# DRV8301.net
KiCad netlist of a schematic drawn in Altium Designer
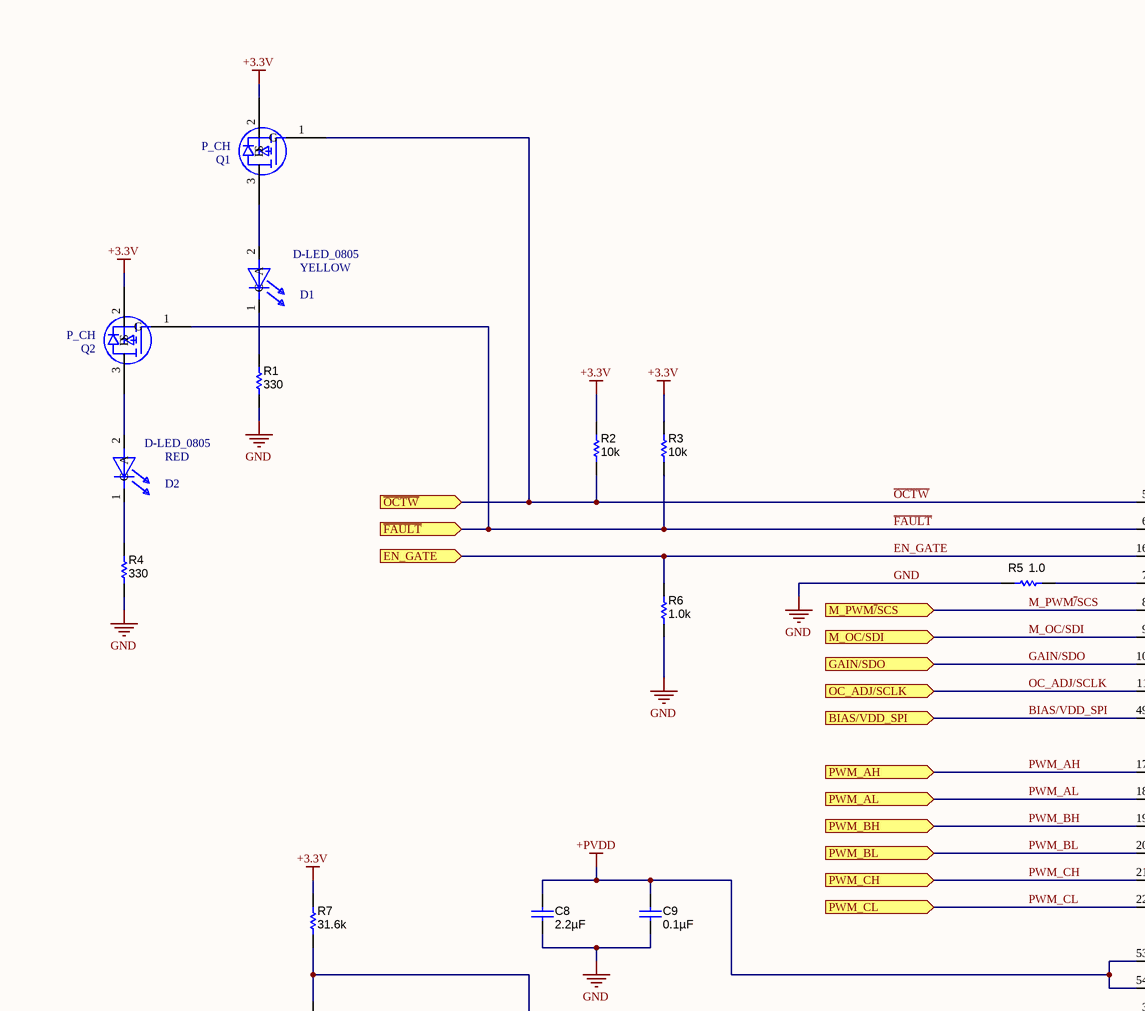
[diagram p0: DRV8301.SchDoc, top left]
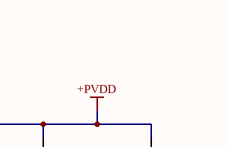
[diagram p1: DRV8301.SchDoc, top right]
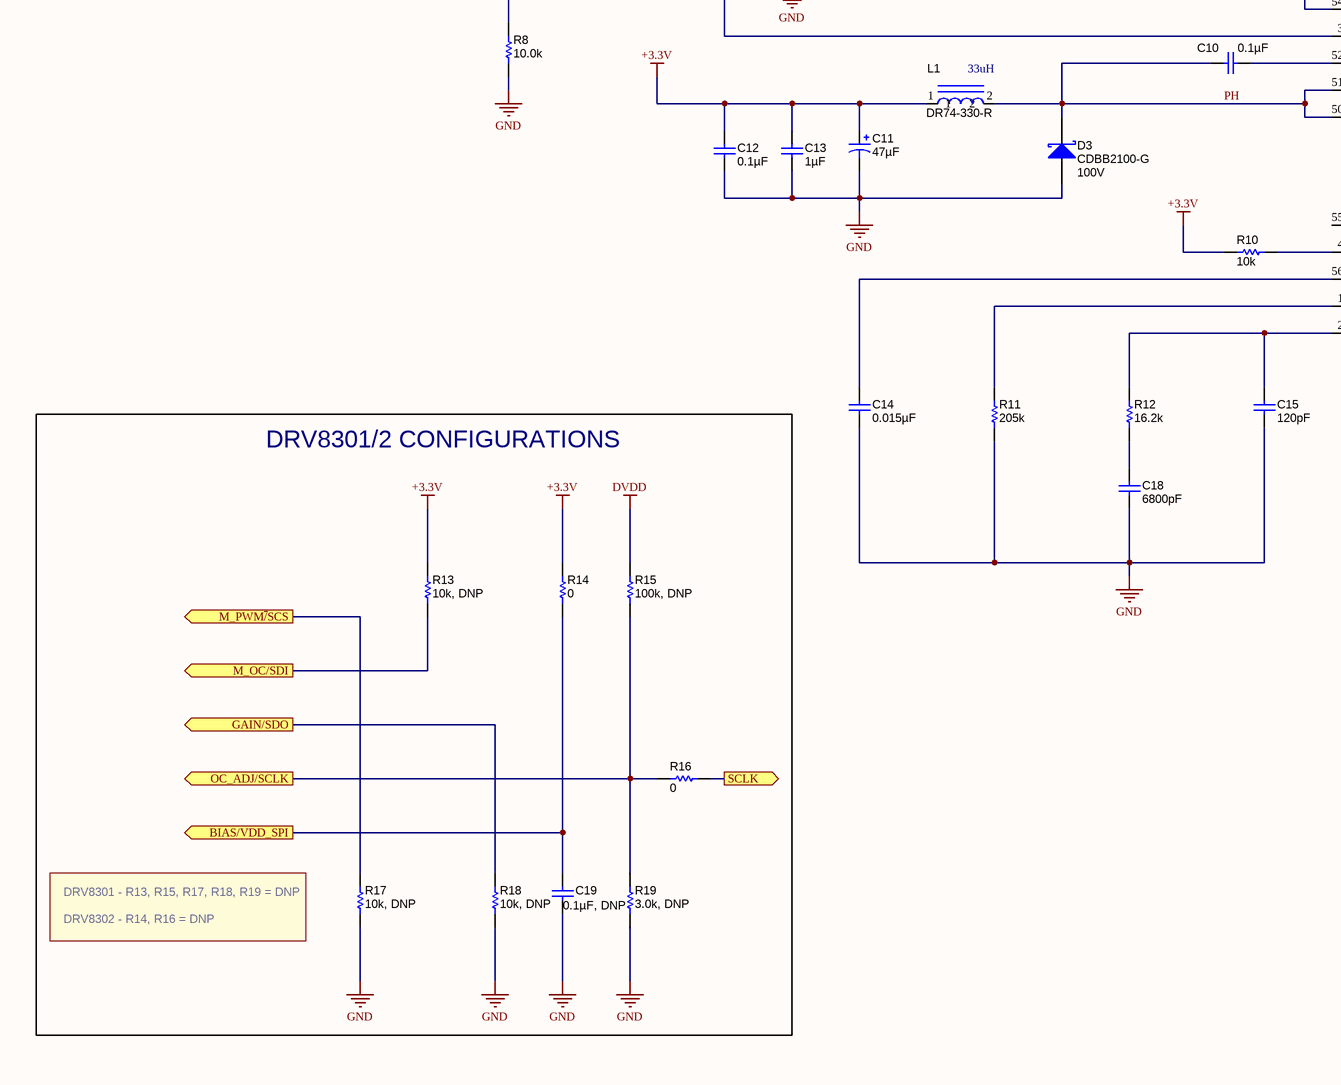
[diagram p2: DRV8301.SchDoc, bottom left]
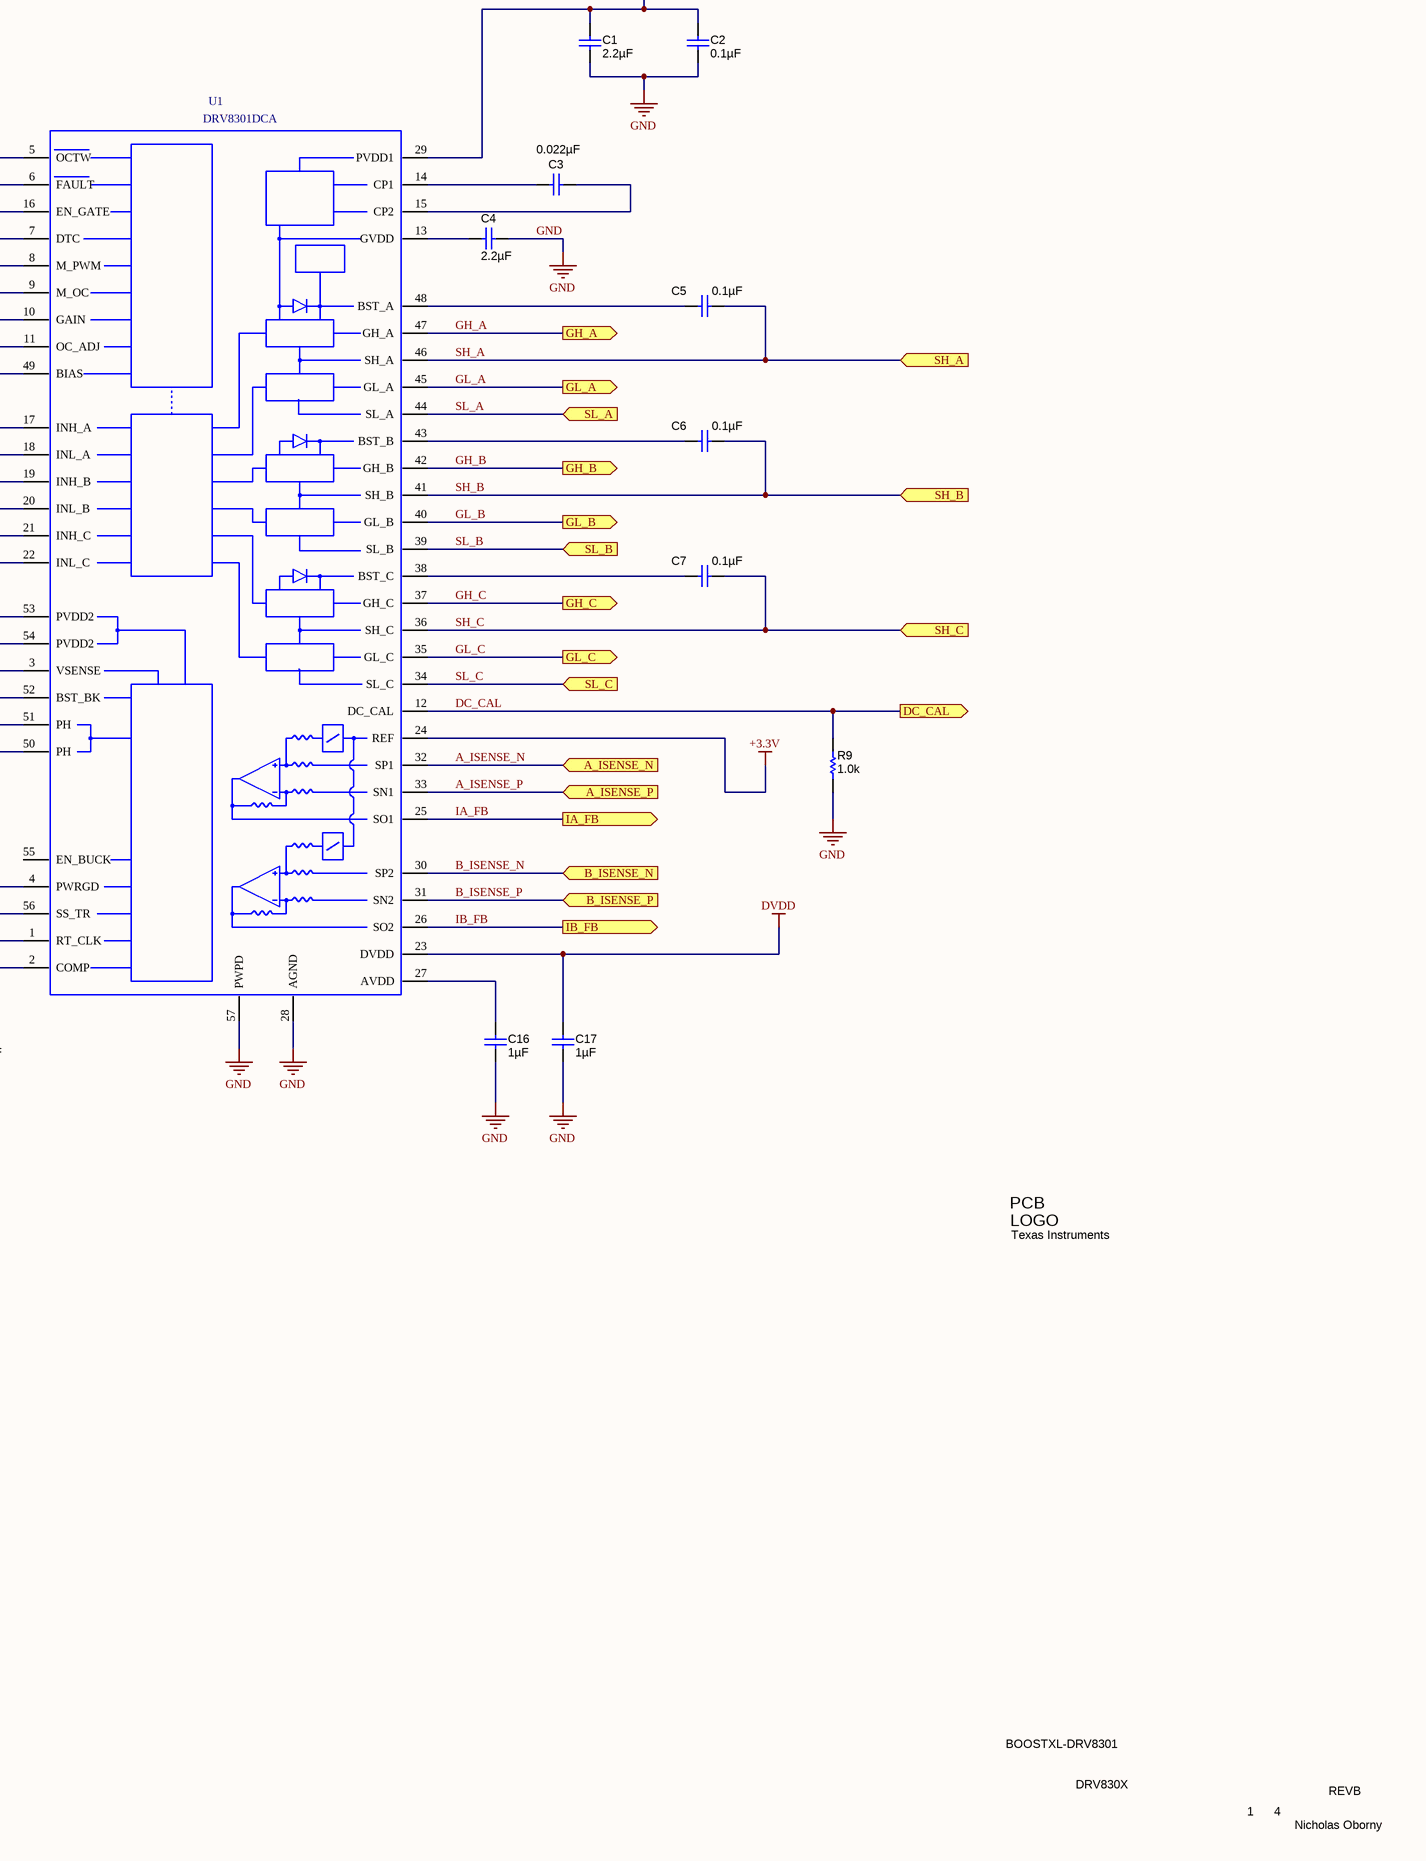
[diagram p3: DRV8301.SchDoc, bottom right]

(export (version "E")
  (design (tool "Eeschema 10.0.6"))
  (components
    (comp (ref "C1")
      (value "GRM32ER72A225KA35L")
      (footprint "1210L")
      (description "CAP, CERM, 2.2uF, 100V, +/-10%, X7R, 1210")
      (fields
        (field (name "VALUEDISPLAYED") "2.2µF")
        (field (name "MANUFACTURER") "MuRata")
        (field (name "PUBLISHER") "Texas Instruments")
      )
      (libsource (lib "Capacitor_Ceramic") (part "GRM32ER72A225KA35L"))
    )
    (comp (ref "C2")
      (value "GRM188R72A104KA35D")
      (footprint "0603L")
      (description "CAP, CERM, 0.1uF, 100V, +/-10%, X7R, 0603")
      (fields
        (field (name "VALUEDISPLAYED") "0.1µF")
        (field (name "MANUFACTURER") "MuRata")
        (field (name "PUBLISHER") "Texas Instruments")
      )
      (libsource (lib "Capacitor_Ceramic") (part "GRM188R72A104KA35D"))
    )
    (comp (ref "C3")
      (value "C1608X7R1H223K")
      (footprint "0603L")
      (description "CAP, CERM, 0.022uF, 50V, +/-10%, X7R, 0603")
      (fields
        (field (name "VALUEDISPLAYED") "0.022µF")
        (field (name "MANUFACTURER") "TDK")
        (field (name "PUBLISHER") "Texas Instruments")
      )
      (libsource (lib "Capacitor_Ceramic") (part "C1608X7R1H223K"))
    )
    (comp (ref "C4")
      (value "GRM219R61E225KA12D")
      (footprint "0805L")
      (description "CAP, CERM, 2.2uF, 25V, +/-10%, X5R, 0805")
      (fields
        (field (name "VALUEDISPLAYED") "2.2µF")
        (field (name "MANUFACTURER") "MuRata")
        (field (name "PUBLISHER") "Texas Instruments")
      )
      (libsource (lib "Capacitor_Ceramic") (part "GRM219R61E225KA12D"))
    )
    (comp (ref "C5")
      (value "C1608X7R1H104K")
      (footprint "0603L")
      (description "CAP, CERM, 0.1uF, 50V, +/-10%, X7R, 0603")
      (fields
        (field (name "VALUEDISPLAYED") "0.1µF")
        (field (name "MANUFACTURER") "TDK")
        (field (name "PUBLISHER") "Texas Instruments")
      )
      (libsource (lib "Capacitor_Ceramic") (part "C1608X7R1H104K"))
    )
    (comp (ref "C6")
      (value "C1608X7R1H104K")
      (footprint "0603L")
      (description "CAP, CERM, 0.1uF, 50V, +/-10%, X7R, 0603")
      (fields
        (field (name "VALUEDISPLAYED") "0.1µF")
        (field (name "MANUFACTURER") "TDK")
        (field (name "PUBLISHER") "Texas Instruments")
      )
      (libsource (lib "Capacitor_Ceramic") (part "C1608X7R1H104K"))
    )
    (comp (ref "C7")
      (value "C1608X7R1H104K")
      (footprint "0603L")
      (description "CAP, CERM, 0.1uF, 50V, +/-10%, X7R, 0603")
      (fields
        (field (name "VALUEDISPLAYED") "0.1µF")
        (field (name "MANUFACTURER") "TDK")
        (field (name "PUBLISHER") "Texas Instruments")
      )
      (libsource (lib "Capacitor_Ceramic") (part "C1608X7R1H104K"))
    )
    (comp (ref "C8")
      (value "GRM32ER72A225KA35L")
      (footprint "1210L")
      (description "CAP, CERM, 2.2uF, 100V, +/-10%, X7R, 1210")
      (fields
        (field (name "VALUEDISPLAYED") "2.2µF")
        (field (name "MANUFACTURER") "MuRata")
        (field (name "PUBLISHER") "Texas Instruments")
      )
      (libsource (lib "Capacitor_Ceramic") (part "GRM32ER72A225KA35L"))
    )
    (comp (ref "C9")
      (value "GRM188R72A104KA35D")
      (footprint "0603L")
      (description "CAP, CERM, 0.1uF, 100V, +/-10%, X7R, 0603")
      (fields
        (field (name "VALUEDISPLAYED") "0.1µF")
        (field (name "MANUFACTURER") "MuRata")
        (field (name "PUBLISHER") "Texas Instruments")
      )
      (libsource (lib "Capacitor_Ceramic") (part "GRM188R72A104KA35D"))
    )
    (comp (ref "C10")
      (value "C1608X7R1H104K")
      (footprint "0603L")
      (description "CAP, CERM, 0.1uF, 50V, +/-10%, X7R, 0603")
      (fields
        (field (name "VALUEDISPLAYED") "0.1µF")
        (field (name "MANUFACTURER") "TDK")
        (field (name "PUBLISHER") "Texas Instruments")
      )
      (libsource (lib "Capacitor_Ceramic") (part "C1608X7R1H104K"))
    )
    (comp (ref "C11")
      (value "EEE-FK1E470P")
      (footprint "SM_RADIAL_D")
      (description "CAP, AL, 47uF, 25V, +/-20%, 0.36 ohm, SMD")
      (fields
        (field (name "VALUEDISPLAYED") "47µF")
        (field (name "MANUFACTURER") "Panasonic")
        (field (name "PUBLISHER") "Texas Instruments")
      )
      (libsource (lib "Capacitor_Aluminum") (part "EEE-FK1E470P"))
    )
    (comp (ref "C12")
      (value "C1608X7R1E104K")
      (footprint "0603L")
      (description "CAP, CERM, 0.1uF, 25V, +/-10%, X7R, 0603")
      (fields
        (field (name "VALUEDISPLAYED") "0.1µF")
        (field (name "MANUFACTURER") "TDK")
        (field (name "PUBLISHER") "Texas Instruments")
      )
      (libsource (lib "Capacitor_Ceramic") (part "C1608X7R1E104K"))
    )
    (comp (ref "C13")
      (value "C1608X5R1E105K080AC")
      (footprint "0603L")
      (description "CAP, CERM, 1uF, 25V, +/-10%, X5R, 0603")
      (fields
        (field (name "VALUEDISPLAYED") "1µF")
        (field (name "MANUFACTURER") "TDK")
        (field (name "PUBLISHER") "Texas Instruments")
      )
      (libsource (lib "Capacitor_Ceramic") (part "C1608X5R1E105K080AC"))
    )
    (comp (ref "C14")
      (value "GRM188R71H153KA01D")
      (footprint "0603L")
      (description "CAP, CERM, 0.015uF, 50V, +/-10%, X7R, 0603")
      (fields
        (field (name "VALUEDISPLAYED") "0.015µF")
        (field (name "MANUFACTURER") "MuRata")
        (field (name "PUBLISHER") "Texas Instruments")
      )
      (libsource (lib "Capacitor_Ceramic") (part "GRM188R71H153KA01D"))
    )
    (comp (ref "C15")
      (value "GRM1885C1H121JA01D")
      (footprint "0603L")
      (description "CAP, CERM, 120pF, 50V, +/-5%, C0G/NP0, 0603")
      (fields
        (field (name "VALUEDISPLAYED") "120pF")
        (field (name "MANUFACTURER") "MuRata")
        (field (name "PUBLISHER") "Texas Instruments")
      )
      (libsource (lib "Capacitor_Ceramic") (part "GRM1885C1H121JA01D"))
    )
    (comp (ref "C16")
      (value "GRM188R61E105KA12D")
      (footprint "0603L")
      (description "CAP, CERM, 1uF, 25V, +/-10%, X5R, 0603")
      (fields
        (field (name "VALUEDISPLAYED") "1µF")
        (field (name "MANUFACTURER") "MuRata")
        (field (name "PUBLISHER") "Texas Instruments")
      )
      (libsource (lib "Capacitor_Ceramic") (part "GRM188R61E105KA12D"))
    )
    (comp (ref "C17")
      (value "GRM188R61E105KA12D")
      (footprint "0603L")
      (description "CAP, CERM, 1uF, 25V, +/-10%, X5R, 0603")
      (fields
        (field (name "VALUEDISPLAYED") "1µF")
        (field (name "MANUFACTURER") "MuRata")
        (field (name "PUBLISHER") "Texas Instruments")
      )
      (libsource (lib "Capacitor_Ceramic") (part "GRM188R61E105KA12D"))
    )
    (comp (ref "C18")
      (value "GRM188R71H682KA01D")
      (footprint "0603L")
      (description "CAP, CERM, 6800pF, 50V, +/-10%, X7R, 0603")
      (fields
        (field (name "VALUEDISPLAYED") "6800pF")
        (field (name "MANUFACTURER") "MuRata")
        (field (name "PUBLISHER") "Texas Instruments")
      )
      (libsource (lib "Capacitor_Ceramic") (part "GRM188R71H682KA01D"))
    )
    (comp (ref "C19")
      (value "C1608X7R1E104K")
      (footprint "0603L")
      (description "CAP, CERM, 0.1uF, 25V, +/-10%, X7R, 0603")
      (fields
        (field (name "VALUEDISPLAYED") "0.1µF, DNP")
        (field (name "MANUFACTURER") "TDK")
        (field (name "PUBLISHER") "Texas Instruments")
      )
      (libsource (lib "Capacitor_Ceramic") (part "C1608X7R1E104K"))
    )
    (comp (ref "D1")
      (value "D-LED_0805")
      (footprint "LED_0805")
      (description "LED THIN 585NM YEL DIFF 0805 SMD")
      (fields
        (field (name "PARTNUMBER") "SML-LXT0805YW-TR")
        (field (name "ALTIUM_VALUE") "YELLOW")
        (field (name "MANUFACTURER") "Lumex Opto/Components Inc")
      )
      (libsource (lib "*") (part "D-LED_0805"))
    )
    (comp (ref "D2")
      (value "D-LED_0805")
      (footprint "LED_0805")
      (description "LED THIN660NM SUPRED DIFF0805SMD")
      (fields
        (field (name "PARTNUMBER") "SML-LXT0805SRW-TR")
        (field (name "ALTIUM_VALUE") "RED")
        (field (name "MANUFACTURER") "Lumex Opto/Components Inc")
      )
      (libsource (lib "*") (part "D-LED_0805"))
    )
    (comp (ref "D3")
      (value "CDBB2100-G")
      (footprint "SMB")
      (description "Diode, Schottky, 100V, 2A, SMB")
      (fields
        (field (name "ALTIUM_VALUE") "100V")
        (field (name "MANUFACTURER") "Comchip Technology")
        (field (name "PUBLISHER") "Texas Instruments")
      )
      (libsource (lib "Diode") (part "CDBC5100-G"))
    )
    (comp (ref "L1")
      (value "DR74-330-R")
      (footprint "IND_DR74")
      (description "INDUCTOR SHIELD PWR 33UH SMD")
      (fields (field (name "MANUFACTURER") "Cooper Bussmann") (field (name "ALTIUM_VALUE") "33uH"))
      (libsource (lib "PADSlegacy_Passive") (part "IND_DR74-XXX"))
    )
    (comp (ref "Logo1")
      (value "Texas Instruments")
      (footprint "TI_Symbol_Overlay_Small")
      (description "Texas Instrument Corporate Signature")
      (fields (field (name "SYMBOLCREATOR") "codlsc") (field (name "PUBLISHER") "Texas Instruments"))
      (libsource (lib "Logos") (part "TI_Logo"))
    )
    (comp (ref "Q1")
      (value "P_CH")
      (footprint "SOT-23")
      (description "MOSFET P-CH 8V 5.4A SOT23-3")
      (fields (field (name "PARTNUMBER") "SI2325DS-T1-E3") (field (name "MANUFACTURER") "Vishey Siliconix"))
      (libsource (lib "*") (part "TR_PFET_SOT23"))
    )
    (comp (ref "Q2")
      (value "P_CH")
      (footprint "SOT-23")
      (description "MOSFET P-CH 8V 5.4A SOT23-3")
      (fields (field (name "PARTNUMBER") "SI2325DS-T1-E3") (field (name "MANUFACTURER") "Vishey Siliconix"))
      (libsource (lib "*") (part "TR_PFET_SOT23"))
    )
    (comp (ref "R1")
      (value "330")
      (footprint "0603L")
      (description "RES, 330 ohm, 5%, 0.1W, 0603")
      (fields
        (field (name "PARTNUMBER") "CRCW0603330RJNEA")
        (field (name "MANUFACTURER") "Vishay-Dale")
        (field (name "PUBLISHER") "Texas Instruments")
      )
      (libsource (lib "Resistor_0603") (part "CRCW0603330RJNEA"))
    )
    (comp (ref "R2")
      (value "10k")
      (footprint "0603L")
      (description "RES, 10k ohm, 5%, 0.1W, 0603")
      (fields
        (field (name "PARTNUMBER") "CRCW060310K0JNEA")
        (field (name "MANUFACTURER") "Vishay-Dale")
        (field (name "PUBLISHER") "Texas Instruments")
      )
      (libsource (lib "Resistor_0603") (part "CRCW060310K0JNEA"))
    )
    (comp (ref "R3")
      (value "10k")
      (footprint "0603L")
      (description "RES, 10k ohm, 5%, 0.1W, 0603")
      (fields
        (field (name "PARTNUMBER") "CRCW060310K0JNEA")
        (field (name "MANUFACTURER") "Vishay-Dale")
        (field (name "PUBLISHER") "Texas Instruments")
      )
      (libsource (lib "Resistor_0603") (part "CRCW060310K0JNEA"))
    )
    (comp (ref "R4")
      (value "330")
      (footprint "0603L")
      (description "RES, 330 ohm, 5%, 0.1W, 0603")
      (fields
        (field (name "PARTNUMBER") "CRCW0603330RJNEA")
        (field (name "MANUFACTURER") "Vishay-Dale")
        (field (name "PUBLISHER") "Texas Instruments")
      )
      (libsource (lib "Resistor_0603") (part "CRCW0603330RJNEA"))
    )
    (comp (ref "R5")
      (value "1.0")
      (footprint "0603L")
      (description "RES, 1.0 ohm, 5%, 0.1W, 0603")
      (fields
        (field (name "PARTNUMBER") "CRCW06031R00JNEA")
        (field (name "MANUFACTURER") "Vishay-Dale")
        (field (name "PUBLISHER") "Texas Instruments")
      )
      (libsource (lib "Resistor_0603") (part "CRCW06031R00JNEA"))
    )
    (comp (ref "R6")
      (value "1.0k")
      (footprint "0603L")
      (description "RES, 1.0k ohm, 5%, 0.1W, 0603")
      (fields
        (field (name "PARTNUMBER") "CRCW06031K00JNEA")
        (field (name "MANUFACTURER") "Vishay-Dale")
        (field (name "PUBLISHER") "Texas Instruments")
      )
      (libsource (lib "Resistor_0603") (part "CRCW06031K00JNEA"))
    )
    (comp (ref "R7")
      (value "31.6k")
      (footprint "0603L")
      (description "RES, 31.6k ohm, 1%, 0.1W, 0603")
      (fields
        (field (name "PARTNUMBER") "CRCW060331K6FKEA")
        (field (name "MANUFACTURER") "Vishay-Dale")
        (field (name "PUBLISHER") "Texas Instruments")
      )
      (libsource (lib "Resistor_0603") (part "CRCW060331K6FKEA"))
    )
    (comp (ref "R8")
      (value "10.0k")
      (footprint "0603L")
      (description "RES, 10.0k ohm, 0.1%, 0.1W, 0603")
      (fields
        (field (name "PARTNUMBER") "RG1608P-103-B-T5")
        (field (name "MANUFACTURER") "Susumu Co Ltd")
        (field (name "PUBLISHER") "Texas Instruments")
      )
      (libsource (lib "Resistor_0603") (part "RG1608P-103-B-T5"))
    )
    (comp (ref "R9")
      (value "1.0k")
      (footprint "0603L")
      (description "RES, 1.0k ohm, 5%, 0.1W, 0603")
      (fields
        (field (name "PARTNUMBER") "CRCW06031K00JNEA")
        (field (name "MANUFACTURER") "Vishay-Dale")
        (field (name "PUBLISHER") "Texas Instruments")
      )
      (libsource (lib "Resistor_0603") (part "CRCW06031K00JNEA"))
    )
    (comp (ref "R10")
      (value "10k")
      (footprint "0603L")
      (description "RES, 10k ohm, 5%, 0.1W, 0603")
      (fields
        (field (name "PARTNUMBER") "CRCW060310K0JNEA")
        (field (name "MANUFACTURER") "Vishay-Dale")
        (field (name "PUBLISHER") "Texas Instruments")
      )
      (libsource (lib "Resistor_0603") (part "CRCW060310K0JNEA"))
    )
    (comp (ref "R11")
      (value "205k")
      (footprint "0603L")
      (description "RES, 205k ohm, 1%, 0.1W, 0603")
      (fields
        (field (name "PARTNUMBER") "CRCW0603205KFKEA")
        (field (name "MANUFACTURER") "Vishay-Dale")
        (field (name "PUBLISHER") "Texas Instruments")
      )
      (libsource (lib "Resistor_0603") (part "CRCW0603205KFKEA"))
    )
    (comp (ref "R12")
      (value "16.2k")
      (footprint "0603L")
      (description "RES, 16.2k ohm, 1%, 0.1W, 0603")
      (fields
        (field (name "PARTNUMBER") "CRCW060316K2FKEA")
        (field (name "MANUFACTURER") "Vishay-Dale")
        (field (name "PUBLISHER") "Texas Instruments")
      )
      (libsource (lib "Resistor_0603") (part "CRCW060316K2FKEA"))
    )
    (comp (ref "R13")
      (value "10k, DNP")
      (footprint "0603L")
      (description "RES, 10k ohm, 5%, 0.1W, 0603")
      (fields
        (field (name "PARTNUMBER") "CRCW060310K0JNEA")
        (field (name "MANUFACTURER") "Vishay-Dale")
        (field (name "PUBLISHER") "Texas Instruments")
      )
      (libsource (lib "Resistor_0603") (part "CRCW060310K0JNEA"))
    )
    (comp (ref "R14")
      (value "0")
      (footprint "0603L")
      (description "RES, 0 ohm, 5%, 0.1W, 0603")
      (fields
        (field (name "PARTNUMBER") "CRCW06030000Z0EA")
        (field (name "MANUFACTURER") "Vishay-Dale")
        (field (name "PUBLISHER") "Texas Instruments")
      )
      (libsource (lib "Resistor_0603") (part "CRCW06030000Z0EA"))
    )
    (comp (ref "R15")
      (value "100k, DNP")
      (footprint "0603L")
      (description "RES, 100k ohm, 5%, 0.1W, 0603")
      (fields
        (field (name "PARTNUMBER") "CRCW0603100KJNEA")
        (field (name "MANUFACTURER") "Vishay-Dale")
        (field (name "PUBLISHER") "Texas Instruments")
      )
      (libsource (lib "Resistor_0603") (part "CRCW0603100KJNEA"))
    )
    (comp (ref "R16")
      (value "0")
      (footprint "0603L")
      (description "RES, 0 ohm, 5%, 0.1W, 0603")
      (fields
        (field (name "PARTNUMBER") "CRCW06030000Z0EA")
        (field (name "MANUFACTURER") "Vishay-Dale")
        (field (name "PUBLISHER") "Texas Instruments")
      )
      (libsource (lib "Resistor_0603") (part "CRCW06030000Z0EA"))
    )
    (comp (ref "R17")
      (value "10k, DNP")
      (footprint "0603L")
      (description "RES, 10k ohm, 5%, 0.1W, 0603")
      (fields
        (field (name "PARTNUMBER") "CRCW060310K0JNEA")
        (field (name "MANUFACTURER") "Vishay-Dale")
        (field (name "PUBLISHER") "Texas Instruments")
      )
      (libsource (lib "Resistor_0603") (part "CRCW060310K0JNEA"))
    )
    (comp (ref "R18")
      (value "10k, DNP")
      (footprint "0603L")
      (description "RES, 10k ohm, 5%, 0.1W, 0603")
      (fields
        (field (name "PARTNUMBER") "CRCW060310K0JNEA")
        (field (name "MANUFACTURER") "Vishay-Dale")
        (field (name "PUBLISHER") "Texas Instruments")
      )
      (libsource (lib "Resistor_0603") (part "CRCW060310K0JNEA"))
    )
    (comp (ref "R19")
      (value "3.0k, DNP")
      (footprint "0603L")
      (description "RES, 3.0k ohm, 5%, 0.1W, 0603")
      (fields
        (field (name "PARTNUMBER") "CRCW06033K00JNEA")
        (field (name "MANUFACTURER") "Vishay-Dale")
        (field (name "PUBLISHER") "Texas Instruments")
      )
      (libsource (lib "Resistor_0603") (part "CRCW06033K00JNEA"))
    )
    (comp (ref "U1")
      (value "DRV8301DCA")
      (footprint "DCA_56P")
      (description "IC, 3 Phase Pre-Driver with Dual Current Shunt Amplifiers and Buck Regulator-Hardware Controlled")
      (fields (field (name "MANUFACTURER") "Texas Instruments") (field (name "VENDOR PART #") "Supplied"))
      (libsource (lib "*") (part "DRV8302DCA_ERIC"))
    )
  )
  (nets
    (net (code "1") (name "+3.3V") (class "Default")
      (node (ref "C11") (pin "1") (pinfunction "+_1") (pintype "passive"))
      (node (ref "C12") (pin "1") (pinfunction "1_1") (pintype "passive"))
      (node (ref "C13") (pin "1") (pinfunction "1_1") (pintype "passive"))
      (node (ref "L1") (pin "1") (pinfunction "1_1") (pintype "passive"))
      (node (ref "Q1") (pin "2") (pinfunction "S_2") (pintype "passive"))
      (node (ref "Q2") (pin "2") (pinfunction "S_2") (pintype "passive"))
      (node (ref "R10") (pin "2") (pinfunction "2_2") (pintype "passive"))
      (node (ref "R13") (pin "2") (pinfunction "2_2") (pintype "passive"))
      (node (ref "R14") (pin "2") (pinfunction "2_2") (pintype "passive"))
      (node (ref "R2") (pin "2") (pinfunction "2_2") (pintype "passive"))
      (node (ref "R3") (pin "2") (pinfunction "2_2") (pintype "passive"))
      (node (ref "R7") (pin "2") (pinfunction "2_2") (pintype "passive"))
      (node (ref "U1") (pin "24") (pinfunction "REF_24") (pintype "passive"))
    )
    (net (code "2") (name "+PVDD") (class "Default")
      (node (ref "C1") (pin "1") (pinfunction "1_1") (pintype "passive"))
      (node (ref "C2") (pin "1") (pinfunction "1_1") (pintype "passive"))
      (node (ref "C8") (pin "1") (pinfunction "1_1") (pintype "passive"))
      (node (ref "C9") (pin "1") (pinfunction "1_1") (pintype "passive"))
      (node (ref "U1") (pin "29") (pinfunction "PVDD1_29") (pintype "passive"))
      (node (ref "U1") (pin "53") (pinfunction "PVDD2_53") (pintype "passive"))
      (node (ref "U1") (pin "54") (pinfunction "PVDD2_54") (pintype "passive"))
    )
    (net (code "3") (name "/A_ISENSE_N") (class "Default")
      (node (ref "U1") (pin "32") (pinfunction "SP1_32") (pintype "passive"))
    )
    (net (code "4") (name "/A_ISENSE_P") (class "Default")
      (node (ref "U1") (pin "33") (pinfunction "SN1_33") (pintype "passive"))
    )
    (net (code "5") (name "/BIAS{slash}VDD_SPI") (class "Default")
      (node (ref "C19") (pin "1") (pinfunction "1_1") (pintype "passive"))
      (node (ref "R14") (pin "1") (pinfunction "1_1") (pintype "passive"))
      (node (ref "U1") (pin "49") (pinfunction "BIAS_49") (pintype "passive"))
    )
    (net (code "6") (name "/B_ISENSE_N") (class "Default")
      (node (ref "U1") (pin "30") (pinfunction "SP2_30") (pintype "passive"))
    )
    (net (code "7") (name "/B_ISENSE_P") (class "Default")
      (node (ref "U1") (pin "31") (pinfunction "SN2_31") (pintype "passive"))
    )
    (net (code "8") (name "/DC_CAL") (class "Default")
      (node (ref "R9") (pin "2") (pinfunction "2_2") (pintype "passive"))
      (node (ref "U1") (pin "12") (pinfunction "DC_CAL_12") (pintype "passive"))
    )
    (net (code "9") (name "/EN_GATE") (class "Default")
      (node (ref "R6") (pin "2") (pinfunction "2_2") (pintype "passive"))
      (node (ref "U1") (pin "16") (pinfunction "EN_GATE_16") (pintype "passive"))
    )
    (net (code "10") (name "/FAULT") (class "Default")
      (node (ref "Q2") (pin "1") (pinfunction "G_1") (pintype "passive"))
      (node (ref "R3") (pin "1") (pinfunction "1_1") (pintype "passive"))
      (node (ref "U1") (pin "6") (pinfunction "FAULT_6") (pintype "passive"))
    )
    (net (code "11") (name "/GAIN{slash}SDO") (class "Default")
      (node (ref "R18") (pin "2") (pinfunction "2_2") (pintype "passive"))
      (node (ref "U1") (pin "10") (pinfunction "GAIN_10") (pintype "passive"))
    )
    (net (code "12") (name "/GH_A") (class "Default")
      (node (ref "U1") (pin "47") (pinfunction "GH_A_47") (pintype "passive"))
    )
    (net (code "13") (name "/GH_B") (class "Default")
      (node (ref "U1") (pin "42") (pinfunction "GH_B_42") (pintype "passive"))
    )
    (net (code "14") (name "/GH_C") (class "Default")
      (node (ref "U1") (pin "37") (pinfunction "GH_C_37") (pintype "passive"))
    )
    (net (code "15") (name "/GL_A") (class "Default")
      (node (ref "U1") (pin "45") (pinfunction "GL_A_45") (pintype "passive"))
    )
    (net (code "16") (name "/GL_B") (class "Default")
      (node (ref "U1") (pin "40") (pinfunction "GL_B_40") (pintype "passive"))
    )
    (net (code "17") (name "/GL_C") (class "Default")
      (node (ref "U1") (pin "35") (pinfunction "GL_C_35") (pintype "passive"))
    )
    (net (code "18") (name "/IA_FB") (class "Default")
      (node (ref "U1") (pin "25") (pinfunction "SO1_25") (pintype "passive"))
    )
    (net (code "19") (name "/IB_FB") (class "Default")
      (node (ref "U1") (pin "26") (pinfunction "SO2_26") (pintype "passive"))
    )
    (net (code "20") (name "/M_OC{slash}SDI") (class "Default")
      (node (ref "R13") (pin "1") (pinfunction "1_1") (pintype "passive"))
      (node (ref "U1") (pin "9") (pinfunction "M_OC_9") (pintype "passive"))
    )
    (net (code "21") (name "/M_PWM~{{slash}}SCS") (class "Default")
      (node (ref "R17") (pin "2") (pinfunction "2_2") (pintype "passive"))
      (node (ref "U1") (pin "8") (pinfunction "M_PWM_8") (pintype "passive"))
    )
    (net (code "22") (name "/OCTW") (class "Default")
      (node (ref "Q1") (pin "1") (pinfunction "G_1") (pintype "passive"))
      (node (ref "R2") (pin "1") (pinfunction "1_1") (pintype "passive"))
      (node (ref "U1") (pin "5") (pinfunction "OCTW_5") (pintype "passive"))
    )
    (net (code "23") (name "/OC_ADJ{slash}SCLK") (class "Default")
      (node (ref "R15") (pin "2") (pinfunction "2_2") (pintype "passive"))
      (node (ref "R16") (pin "2") (pinfunction "2_2") (pintype "passive"))
      (node (ref "R19") (pin "2") (pinfunction "2_2") (pintype "passive"))
      (node (ref "U1") (pin "11") (pinfunction "OC_ADJ_11") (pintype "passive"))
    )
    (net (code "24") (name "/PH") (class "Default")
      (node (ref "C10") (pin "1") (pinfunction "1_1") (pintype "passive"))
      (node (ref "D3") (pin "1") (pinfunction "K_1") (pintype "passive"))
      (node (ref "L1") (pin "2") (pinfunction "2_2") (pintype "passive"))
      (node (ref "U1") (pin "50") (pinfunction "PH_50") (pintype "passive"))
      (node (ref "U1") (pin "51") (pinfunction "PH_51") (pintype "passive"))
    )
    (net (code "25") (name "/PWM_AH") (class "Default")
      (node (ref "U1") (pin "17") (pinfunction "INH_A_17") (pintype "passive"))
    )
    (net (code "26") (name "/PWM_AL") (class "Default")
      (node (ref "U1") (pin "18") (pinfunction "INL_A_18") (pintype "passive"))
    )
    (net (code "27") (name "/PWM_BH") (class "Default")
      (node (ref "U1") (pin "19") (pinfunction "INH_B_19") (pintype "passive"))
    )
    (net (code "28") (name "/PWM_BL") (class "Default")
      (node (ref "U1") (pin "20") (pinfunction "INL_B_20") (pintype "passive"))
    )
    (net (code "29") (name "/PWM_CH") (class "Default")
      (node (ref "U1") (pin "21") (pinfunction "INH_C_21") (pintype "passive"))
    )
    (net (code "30") (name "/PWM_CL") (class "Default")
      (node (ref "U1") (pin "22") (pinfunction "INL_C_22") (pintype "passive"))
    )
    (net (code "31") (name "/SCLK") (class "Default")
      (node (ref "R16") (pin "1") (pinfunction "1_1") (pintype "passive"))
    )
    (net (code "32") (name "/SH_A") (class "Default")
      (node (ref "C5") (pin "2") (pinfunction "2_2") (pintype "passive"))
      (node (ref "U1") (pin "46") (pinfunction "SH_A_46") (pintype "passive"))
    )
    (net (code "33") (name "/SH_B") (class "Default")
      (node (ref "C6") (pin "2") (pinfunction "2_2") (pintype "passive"))
      (node (ref "U1") (pin "41") (pinfunction "SH_B_41") (pintype "passive"))
    )
    (net (code "34") (name "/SH_C") (class "Default")
      (node (ref "C7") (pin "2") (pinfunction "2_2") (pintype "passive"))
      (node (ref "U1") (pin "36") (pinfunction "SH_C_36") (pintype "passive"))
    )
    (net (code "35") (name "/SL_A") (class "Default")
      (node (ref "U1") (pin "44") (pinfunction "SL_A_44") (pintype "passive"))
    )
    (net (code "36") (name "/SL_B") (class "Default")
      (node (ref "U1") (pin "39") (pinfunction "SL_B_39") (pintype "passive"))
    )
    (net (code "37") (name "/SL_C") (class "Default")
      (node (ref "U1") (pin "34") (pinfunction "SL_C_34") (pintype "passive"))
    )
    (net (code "38") (name "DVDD") (class "Default")
      (node (ref "C17") (pin "1") (pinfunction "1_1") (pintype "passive"))
      (node (ref "R15") (pin "1") (pinfunction "1_1") (pintype "passive"))
      (node (ref "U1") (pin "23") (pinfunction "DVDD_23") (pintype "passive"))
    )
    (net (code "39") (name "GND") (class "Default")
      (node (ref "C1") (pin "2") (pinfunction "2_2") (pintype "passive"))
      (node (ref "C11") (pin "2") (pinfunction "-_2") (pintype "passive"))
      (node (ref "C12") (pin "2") (pinfunction "2_2") (pintype "passive"))
      (node (ref "C13") (pin "2") (pinfunction "2_2") (pintype "passive"))
      (node (ref "C14") (pin "2") (pinfunction "2_2") (pintype "passive"))
      (node (ref "C15") (pin "2") (pinfunction "2_2") (pintype "passive"))
      (node (ref "C16") (pin "2") (pinfunction "2_2") (pintype "passive"))
      (node (ref "C17") (pin "2") (pinfunction "2_2") (pintype "passive"))
      (node (ref "C18") (pin "2") (pinfunction "2_2") (pintype "passive"))
      (node (ref "C19") (pin "2") (pinfunction "2_2") (pintype "passive"))
      (node (ref "C2") (pin "2") (pinfunction "2_2") (pintype "passive"))
      (node (ref "C4") (pin "2") (pinfunction "2_2") (pintype "passive"))
      (node (ref "C8") (pin "2") (pinfunction "2_2") (pintype "passive"))
      (node (ref "C9") (pin "2") (pinfunction "2_2") (pintype "passive"))
      (node (ref "D3") (pin "2") (pinfunction "A_2") (pintype "passive"))
      (node (ref "R1") (pin "1") (pinfunction "1_1") (pintype "passive"))
      (node (ref "R11") (pin "1") (pinfunction "1_1") (pintype "passive"))
      (node (ref "R17") (pin "1") (pinfunction "1_1") (pintype "passive"))
      (node (ref "R18") (pin "1") (pinfunction "1_1") (pintype "passive"))
      (node (ref "R19") (pin "1") (pinfunction "1_1") (pintype "passive"))
      (node (ref "R4") (pin "1") (pinfunction "1_1") (pintype "passive"))
      (node (ref "R5") (pin "1") (pinfunction "1_1") (pintype "passive"))
      (node (ref "R6") (pin "1") (pinfunction "1_1") (pintype "passive"))
      (node (ref "R8") (pin "1") (pinfunction "1_1") (pintype "passive"))
      (node (ref "R9") (pin "1") (pinfunction "1_1") (pintype "passive"))
      (node (ref "U1") (pin "28") (pinfunction "AGND_28") (pintype "passive"))
      (node (ref "U1") (pin "57") (pinfunction "PWPD_57") (pintype "passive"))
    )
    (net (code "40") (name "Net-(C18-Pad1)") (class "Default")
      (node (ref "C18") (pin "1") (pinfunction "1_1") (pintype "passive"))
      (node (ref "R12") (pin "1") (pinfunction "1_1") (pintype "passive"))
    )
    (net (code "41") (name "Net-(D1-A)") (class "Default")
      (node (ref "D1") (pin "2") (pinfunction "A_2") (pintype "passive"))
      (node (ref "Q1") (pin "3") (pinfunction "D_3") (pintype "passive"))
    )
    (net (code "42") (name "Net-(D1-C)") (class "Default")
      (node (ref "D1") (pin "1") (pinfunction "C_1") (pintype "passive"))
      (node (ref "R1") (pin "2") (pinfunction "2_2") (pintype "passive"))
    )
    (net (code "43") (name "Net-(D2-A)") (class "Default")
      (node (ref "D2") (pin "2") (pinfunction "A_2") (pintype "passive"))
      (node (ref "Q2") (pin "3") (pinfunction "D_3") (pintype "passive"))
    )
    (net (code "44") (name "Net-(D2-C)") (class "Default")
      (node (ref "D2") (pin "1") (pinfunction "C_1") (pintype "passive"))
      (node (ref "R4") (pin "2") (pinfunction "2_2") (pintype "passive"))
    )
    (net (code "45") (name "Net-(U1-AVDD)") (class "Default")
      (node (ref "C16") (pin "1") (pinfunction "1_1") (pintype "passive"))
      (node (ref "U1") (pin "27") (pinfunction "AVDD_27") (pintype "passive"))
    )
    (net (code "46") (name "Net-(U1-BST_A)") (class "Default")
      (node (ref "C5") (pin "1") (pinfunction "1_1") (pintype "passive"))
      (node (ref "U1") (pin "48") (pinfunction "BST_A_48") (pintype "passive"))
    )
    (net (code "47") (name "Net-(U1-BST_B)") (class "Default")
      (node (ref "C6") (pin "1") (pinfunction "1_1") (pintype "passive"))
      (node (ref "U1") (pin "43") (pinfunction "BST_B_43") (pintype "passive"))
    )
    (net (code "48") (name "Net-(U1-BST_BK)") (class "Default")
      (node (ref "C10") (pin "2") (pinfunction "2_2") (pintype "passive"))
      (node (ref "U1") (pin "52") (pinfunction "BST_BK_52") (pintype "passive"))
    )
    (net (code "49") (name "Net-(U1-BST_C)") (class "Default")
      (node (ref "C7") (pin "1") (pinfunction "1_1") (pintype "passive"))
      (node (ref "U1") (pin "38") (pinfunction "BST_C_38") (pintype "passive"))
    )
    (net (code "50") (name "Net-(U1-COMP)") (class "Default")
      (node (ref "C15") (pin "1") (pinfunction "1_1") (pintype "passive"))
      (node (ref "R12") (pin "2") (pinfunction "2_2") (pintype "passive"))
      (node (ref "U1") (pin "2") (pinfunction "COMP_2") (pintype "passive"))
    )
    (net (code "51") (name "Net-(U1-CP1)") (class "Default")
      (node (ref "C3") (pin "1") (pinfunction "1_1") (pintype "passive"))
      (node (ref "U1") (pin "14") (pinfunction "CP1_14") (pintype "passive"))
    )
    (net (code "52") (name "Net-(U1-CP2)") (class "Default")
      (node (ref "C3") (pin "2") (pinfunction "2_2") (pintype "passive"))
      (node (ref "U1") (pin "15") (pinfunction "CP2_15") (pintype "passive"))
    )
    (net (code "53") (name "Net-(U1-DTC)") (class "Default")
      (node (ref "R5") (pin "2") (pinfunction "2_2") (pintype "passive"))
      (node (ref "U1") (pin "7") (pinfunction "DTC_7") (pintype "passive"))
    )
    (net (code "54") (name "Net-(U1-GVDD)") (class "Default")
      (node (ref "C4") (pin "1") (pinfunction "1_1") (pintype "passive"))
      (node (ref "U1") (pin "13") (pinfunction "GVDD_13") (pintype "passive"))
    )
    (net (code "55") (name "Net-(U1-PWRGD)") (class "Default")
      (node (ref "R10") (pin "1") (pinfunction "1_1") (pintype "passive"))
      (node (ref "U1") (pin "4") (pinfunction "PWRGD_4") (pintype "passive"))
    )
    (net (code "56") (name "Net-(U1-RT_CLK)") (class "Default")
      (node (ref "R11") (pin "2") (pinfunction "2_2") (pintype "passive"))
      (node (ref "U1") (pin "1") (pinfunction "RT_CLK_1") (pintype "passive"))
    )
    (net (code "57") (name "Net-(U1-SS_TR)") (class "Default")
      (node (ref "C14") (pin "1") (pinfunction "1_1") (pintype "passive"))
      (node (ref "U1") (pin "56") (pinfunction "SS_TR_56") (pintype "passive"))
    )
    (net (code "58") (name "Net-(U1-VSENSE)") (class "Default")
      (node (ref "R7") (pin "1") (pinfunction "1_1") (pintype "passive"))
      (node (ref "R8") (pin "2") (pinfunction "2_2") (pintype "passive"))
      (node (ref "U1") (pin "3") (pinfunction "VSENSE_3") (pintype "passive"))
    )
    (net (code "59") (name "unconnected-(U1-EN_BUCK-Pad55)") (class "Default")
      (node (ref "U1") (pin "55") (pinfunction "EN_BUCK_55") (pintype "passive"))
    )
  )
)
